# 3_-_Drivers.net
KiCad netlist of a schematic drawn in Altium Designer
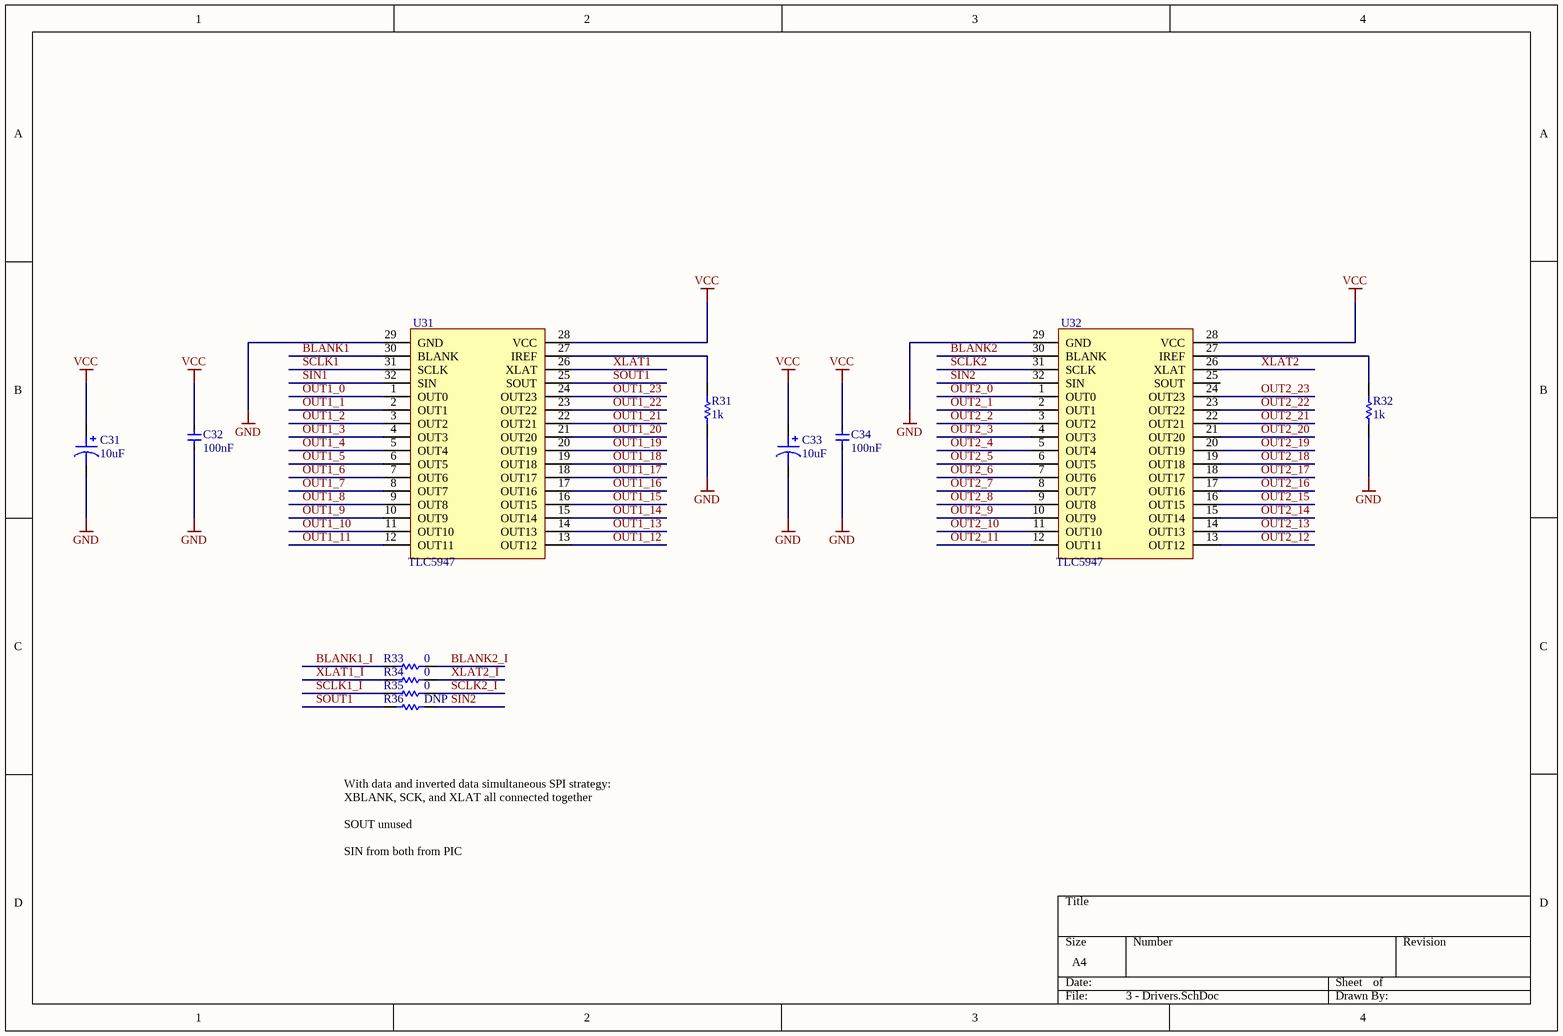
[diagram p0: 3 - Drivers.SchDoc]

(export (version "E")
  (design (tool "Eeschema 10.0.6"))
  (components
    (comp (ref "C31")
      (value "10uF")
      (footprint "CAP_ELEC_5x5.7")
      (description "SMT Polarised Capacitor")
      (libsource (lib "Passives") (part "Polarised Capacitor"))
    )
    (comp (ref "C32")
      (value "100nF")
      (footprint "Passives:CAP 0603/1608")
      (description "Capacitor")
      (fields (field (name "Comment") "Cap_0603"))
      (libsource (lib "SCH_Passive") (part "Cap_0603"))
    )
    (comp (ref "C33")
      (value "10uF")
      (footprint "CAP_ELEC_5x5.7")
      (description "SMT Polarised Capacitor")
      (libsource (lib "Passives") (part "Polarised Capacitor"))
    )
    (comp (ref "C34")
      (value "100nF")
      (footprint "Passives:CAP 0603/1608")
      (description "Capacitor")
      (fields (field (name "Comment") "Cap_0603"))
      (libsource (lib "SCH_Passive") (part "Cap_0603"))
    )
    (comp (ref "R31")
      (value "1k")
      (footprint "RES_0603")
      (description "Resistor")
      (fields (field (name "Comment") "Res1") (field (name "PUBLISHER") "Altium Limited"))
      (libsource (lib "Miscellaneous Devices") (part "Res1"))
    )
    (comp (ref "R32")
      (value "1k")
      (footprint "RES_0603")
      (description "Resistor")
      (fields (field (name "Comment") "Res1") (field (name "PUBLISHER") "Altium Limited"))
      (libsource (lib "Miscellaneous Devices") (part "Res1"))
    )
    (comp (ref "R33")
      (value "0")
      (footprint "RES_0603")
      (description "Resistor")
      (fields (field (name "Comment") "Res1") (field (name "PUBLISHER") "Altium Limited"))
      (libsource (lib "Miscellaneous Devices") (part "Res1"))
    )
    (comp (ref "R34")
      (value "0")
      (footprint "RES_0603")
      (description "Resistor")
      (fields (field (name "Comment") "Res1") (field (name "PUBLISHER") "Altium Limited"))
      (libsource (lib "Miscellaneous Devices") (part "Res1"))
    )
    (comp (ref "R35")
      (value "0")
      (footprint "RES_0603")
      (description "Resistor")
      (fields (field (name "Comment") "Res1") (field (name "PUBLISHER") "Altium Limited"))
      (libsource (lib "Miscellaneous Devices") (part "Res1"))
    )
    (comp (ref "R36")
      (value "DNP")
      (footprint "RES_0603")
      (description "Resistor")
      (fields (field (name "Comment") "Res1") (field (name "PUBLISHER") "Altium Limited"))
      (libsource (lib "Miscellaneous Devices") (part "Res1"))
    )
    (comp (ref "U31")
      (value "TLC5947")
      (footprint "QFN50P500X500X100-33N")
      (description "LED Driver")
      (libsource (lib "SCH_IntegratedCircuit") (part "TLC5947"))
    )
    (comp (ref "U32")
      (value "TLC5947")
      (footprint "QFN50P500X500X100-33N")
      (description "LED Driver")
      (libsource (lib "SCH_IntegratedCircuit") (part "TLC5947"))
    )
  )
  (nets
    (net (code "1") (name "/BLANK1") (class "Default")
      (node (ref "U31") (pin "30") (pinfunction "BLANK_30") (pintype "passive"))
    )
    (net (code "2") (name "/BLANK1_I") (class "Default")
      (node (ref "R33") (pin "2") (pinfunction "2_2") (pintype "passive"))
    )
    (net (code "3") (name "/BLANK2") (class "Default")
      (node (ref "U32") (pin "30") (pinfunction "BLANK_30") (pintype "passive"))
    )
    (net (code "4") (name "/BLANK2_I") (class "Default")
      (node (ref "R33") (pin "1") (pinfunction "1_1") (pintype "passive"))
    )
    (net (code "5") (name "/OUT1_0") (class "Default")
      (node (ref "U31") (pin "1") (pinfunction "OUT0_1") (pintype "passive"))
    )
    (net (code "6") (name "/OUT1_1") (class "Default")
      (node (ref "U31") (pin "2") (pinfunction "OUT1_2") (pintype "passive"))
    )
    (net (code "7") (name "/OUT1_2") (class "Default")
      (node (ref "U31") (pin "3") (pinfunction "OUT2_3") (pintype "passive"))
    )
    (net (code "8") (name "/OUT1_3") (class "Default")
      (node (ref "U31") (pin "4") (pinfunction "OUT3_4") (pintype "passive"))
    )
    (net (code "9") (name "/OUT1_4") (class "Default")
      (node (ref "U31") (pin "5") (pinfunction "OUT4_5") (pintype "passive"))
    )
    (net (code "10") (name "/OUT1_5") (class "Default")
      (node (ref "U31") (pin "6") (pinfunction "OUT5_6") (pintype "passive"))
    )
    (net (code "11") (name "/OUT1_6") (class "Default")
      (node (ref "U31") (pin "7") (pinfunction "OUT6_7") (pintype "passive"))
    )
    (net (code "12") (name "/OUT1_7") (class "Default")
      (node (ref "U31") (pin "8") (pinfunction "OUT7_8") (pintype "passive"))
    )
    (net (code "13") (name "/OUT1_8") (class "Default")
      (node (ref "U31") (pin "9") (pinfunction "OUT8_9") (pintype "passive"))
    )
    (net (code "14") (name "/OUT1_9") (class "Default")
      (node (ref "U31") (pin "10") (pinfunction "OUT9_10") (pintype "passive"))
    )
    (net (code "15") (name "/OUT1_10") (class "Default")
      (node (ref "U31") (pin "11") (pinfunction "OUT10_11") (pintype "passive"))
    )
    (net (code "16") (name "/OUT1_11") (class "Default")
      (node (ref "U31") (pin "12") (pinfunction "OUT11_12") (pintype "passive"))
    )
    (net (code "17") (name "/OUT1_12") (class "Default")
      (node (ref "U31") (pin "13") (pinfunction "OUT12_13") (pintype "passive"))
    )
    (net (code "18") (name "/OUT1_13") (class "Default")
      (node (ref "U31") (pin "14") (pinfunction "OUT13_14") (pintype "passive"))
    )
    (net (code "19") (name "/OUT1_14") (class "Default")
      (node (ref "U31") (pin "15") (pinfunction "OUT14_15") (pintype "passive"))
    )
    (net (code "20") (name "/OUT1_15") (class "Default")
      (node (ref "U31") (pin "16") (pinfunction "OUT15_16") (pintype "passive"))
    )
    (net (code "21") (name "/OUT1_16") (class "Default")
      (node (ref "U31") (pin "17") (pinfunction "OUT16_17") (pintype "passive"))
    )
    (net (code "22") (name "/OUT1_17") (class "Default")
      (node (ref "U31") (pin "18") (pinfunction "OUT17_18") (pintype "passive"))
    )
    (net (code "23") (name "/OUT1_18") (class "Default")
      (node (ref "U31") (pin "19") (pinfunction "OUT18_19") (pintype "passive"))
    )
    (net (code "24") (name "/OUT1_19") (class "Default")
      (node (ref "U31") (pin "20") (pinfunction "OUT19_20") (pintype "passive"))
    )
    (net (code "25") (name "/OUT1_20") (class "Default")
      (node (ref "U31") (pin "21") (pinfunction "OUT20_21") (pintype "passive"))
    )
    (net (code "26") (name "/OUT1_21") (class "Default")
      (node (ref "U31") (pin "22") (pinfunction "OUT21_22") (pintype "passive"))
    )
    (net (code "27") (name "/OUT1_22") (class "Default")
      (node (ref "U31") (pin "23") (pinfunction "OUT22_23") (pintype "passive"))
    )
    (net (code "28") (name "/OUT1_23") (class "Default")
      (node (ref "U31") (pin "24") (pinfunction "OUT23_24") (pintype "passive"))
    )
    (net (code "29") (name "/OUT2_0") (class "Default")
      (node (ref "U32") (pin "1") (pinfunction "OUT0_1") (pintype "passive"))
    )
    (net (code "30") (name "/OUT2_1") (class "Default")
      (node (ref "U32") (pin "2") (pinfunction "OUT1_2") (pintype "passive"))
    )
    (net (code "31") (name "/OUT2_2") (class "Default")
      (node (ref "U32") (pin "3") (pinfunction "OUT2_3") (pintype "passive"))
    )
    (net (code "32") (name "/OUT2_3") (class "Default")
      (node (ref "U32") (pin "4") (pinfunction "OUT3_4") (pintype "passive"))
    )
    (net (code "33") (name "/OUT2_4") (class "Default")
      (node (ref "U32") (pin "5") (pinfunction "OUT4_5") (pintype "passive"))
    )
    (net (code "34") (name "/OUT2_5") (class "Default")
      (node (ref "U32") (pin "6") (pinfunction "OUT5_6") (pintype "passive"))
    )
    (net (code "35") (name "/OUT2_6") (class "Default")
      (node (ref "U32") (pin "7") (pinfunction "OUT6_7") (pintype "passive"))
    )
    (net (code "36") (name "/OUT2_7") (class "Default")
      (node (ref "U32") (pin "8") (pinfunction "OUT7_8") (pintype "passive"))
    )
    (net (code "37") (name "/OUT2_8") (class "Default")
      (node (ref "U32") (pin "9") (pinfunction "OUT8_9") (pintype "passive"))
    )
    (net (code "38") (name "/OUT2_9") (class "Default")
      (node (ref "U32") (pin "10") (pinfunction "OUT9_10") (pintype "passive"))
    )
    (net (code "39") (name "/OUT2_10") (class "Default")
      (node (ref "U32") (pin "11") (pinfunction "OUT10_11") (pintype "passive"))
    )
    (net (code "40") (name "/OUT2_11") (class "Default")
      (node (ref "U32") (pin "12") (pinfunction "OUT11_12") (pintype "passive"))
    )
    (net (code "41") (name "/OUT2_12") (class "Default")
      (node (ref "U32") (pin "13") (pinfunction "OUT12_13") (pintype "passive"))
    )
    (net (code "42") (name "/OUT2_13") (class "Default")
      (node (ref "U32") (pin "14") (pinfunction "OUT13_14") (pintype "passive"))
    )
    (net (code "43") (name "/OUT2_14") (class "Default")
      (node (ref "U32") (pin "15") (pinfunction "OUT14_15") (pintype "passive"))
    )
    (net (code "44") (name "/OUT2_15") (class "Default")
      (node (ref "U32") (pin "16") (pinfunction "OUT15_16") (pintype "passive"))
    )
    (net (code "45") (name "/OUT2_16") (class "Default")
      (node (ref "U32") (pin "17") (pinfunction "OUT16_17") (pintype "passive"))
    )
    (net (code "46") (name "/OUT2_17") (class "Default")
      (node (ref "U32") (pin "18") (pinfunction "OUT17_18") (pintype "passive"))
    )
    (net (code "47") (name "/OUT2_18") (class "Default")
      (node (ref "U32") (pin "19") (pinfunction "OUT18_19") (pintype "passive"))
    )
    (net (code "48") (name "/OUT2_19") (class "Default")
      (node (ref "U32") (pin "20") (pinfunction "OUT19_20") (pintype "passive"))
    )
    (net (code "49") (name "/OUT2_20") (class "Default")
      (node (ref "U32") (pin "21") (pinfunction "OUT20_21") (pintype "passive"))
    )
    (net (code "50") (name "/OUT2_21") (class "Default")
      (node (ref "U32") (pin "22") (pinfunction "OUT21_22") (pintype "passive"))
    )
    (net (code "51") (name "/OUT2_22") (class "Default")
      (node (ref "U32") (pin "23") (pinfunction "OUT22_23") (pintype "passive"))
    )
    (net (code "52") (name "/OUT2_23") (class "Default")
      (node (ref "U32") (pin "24") (pinfunction "OUT23_24") (pintype "passive"))
    )
    (net (code "53") (name "/SCLK1") (class "Default")
      (node (ref "U31") (pin "31") (pinfunction "SCLK_31") (pintype "passive"))
    )
    (net (code "54") (name "/SCLK1_I") (class "Default")
      (node (ref "R35") (pin "2") (pinfunction "2_2") (pintype "passive"))
    )
    (net (code "55") (name "/SCLK2") (class "Default")
      (node (ref "U32") (pin "31") (pinfunction "SCLK_31") (pintype "passive"))
    )
    (net (code "56") (name "/SCLK2_I") (class "Default")
      (node (ref "R35") (pin "1") (pinfunction "1_1") (pintype "passive"))
    )
    (net (code "57") (name "/SIN1") (class "Default")
      (node (ref "U31") (pin "32") (pinfunction "SIN_32") (pintype "passive"))
    )
    (net (code "58") (name "/SIN2") (class "Default")
      (node (ref "R36") (pin "1") (pinfunction "1_1") (pintype "passive"))
      (node (ref "U32") (pin "32") (pinfunction "SIN_32") (pintype "passive"))
    )
    (net (code "59") (name "/SOUT1") (class "Default")
      (node (ref "R36") (pin "2") (pinfunction "2_2") (pintype "passive"))
      (node (ref "U31") (pin "25") (pinfunction "SOUT_25") (pintype "passive"))
    )
    (net (code "60") (name "/XLAT1") (class "Default")
      (node (ref "U31") (pin "26") (pinfunction "XLAT_26") (pintype "passive"))
    )
    (net (code "61") (name "/XLAT1_I") (class "Default")
      (node (ref "R34") (pin "2") (pinfunction "2_2") (pintype "passive"))
    )
    (net (code "62") (name "/XLAT2") (class "Default")
      (node (ref "U32") (pin "26") (pinfunction "XLAT_26") (pintype "passive"))
    )
    (net (code "63") (name "/XLAT2_I") (class "Default")
      (node (ref "R34") (pin "1") (pinfunction "1_1") (pintype "passive"))
    )
    (net (code "64") (name "GND") (class "Default")
      (node (ref "C31") (pin "2") (pinfunction "2_2") (pintype "passive"))
      (node (ref "C32") (pin "1") (pinfunction "1_1") (pintype "passive"))
      (node (ref "C33") (pin "2") (pinfunction "2_2") (pintype "passive"))
      (node (ref "C34") (pin "1") (pinfunction "1_1") (pintype "passive"))
      (node (ref "R31") (pin "1") (pinfunction "1_1") (pintype "passive"))
      (node (ref "R32") (pin "1") (pinfunction "1_1") (pintype "passive"))
      (node (ref "U31") (pin "29") (pinfunction "GND_29") (pintype "passive"))
      (node (ref "U32") (pin "29") (pinfunction "GND_29") (pintype "passive"))
    )
    (net (code "65") (name "Net-(U31-IREF)") (class "Default")
      (node (ref "R31") (pin "2") (pinfunction "2_2") (pintype "passive"))
      (node (ref "U31") (pin "27") (pinfunction "IREF_27") (pintype "passive"))
    )
    (net (code "66") (name "Net-(U32-IREF)") (class "Default")
      (node (ref "R32") (pin "2") (pinfunction "2_2") (pintype "passive"))
      (node (ref "U32") (pin "27") (pinfunction "IREF_27") (pintype "passive"))
    )
    (net (code "67") (name "VCC") (class "Default")
      (node (ref "C31") (pin "1") (pinfunction "1_1") (pintype "passive"))
      (node (ref "C32") (pin "2") (pinfunction "2_2") (pintype "passive"))
      (node (ref "C33") (pin "1") (pinfunction "1_1") (pintype "passive"))
      (node (ref "C34") (pin "2") (pinfunction "2_2") (pintype "passive"))
      (node (ref "U31") (pin "28") (pinfunction "VCC_28") (pintype "passive"))
      (node (ref "U32") (pin "28") (pinfunction "VCC_28") (pintype "passive"))
    )
    (net (code "68") (name "unconnected-(U31-GND-Pad33)") (class "Default")
      (node (ref "U31") (pin "33") (pinfunction "GND_33") (pintype "passive"))
    )
    (net (code "69") (name "unconnected-(U32-GND-Pad33)") (class "Default")
      (node (ref "U32") (pin "33") (pinfunction "GND_33") (pintype "passive"))
    )
    (net (code "70") (name "unconnected-(U32-SOUT-Pad25)") (class "Default")
      (node (ref "U32") (pin "25") (pinfunction "SOUT_25") (pintype "passive"))
    )
  )
)
